# MCU.net
KiCad netlist of a schematic drawn in Altium Designer
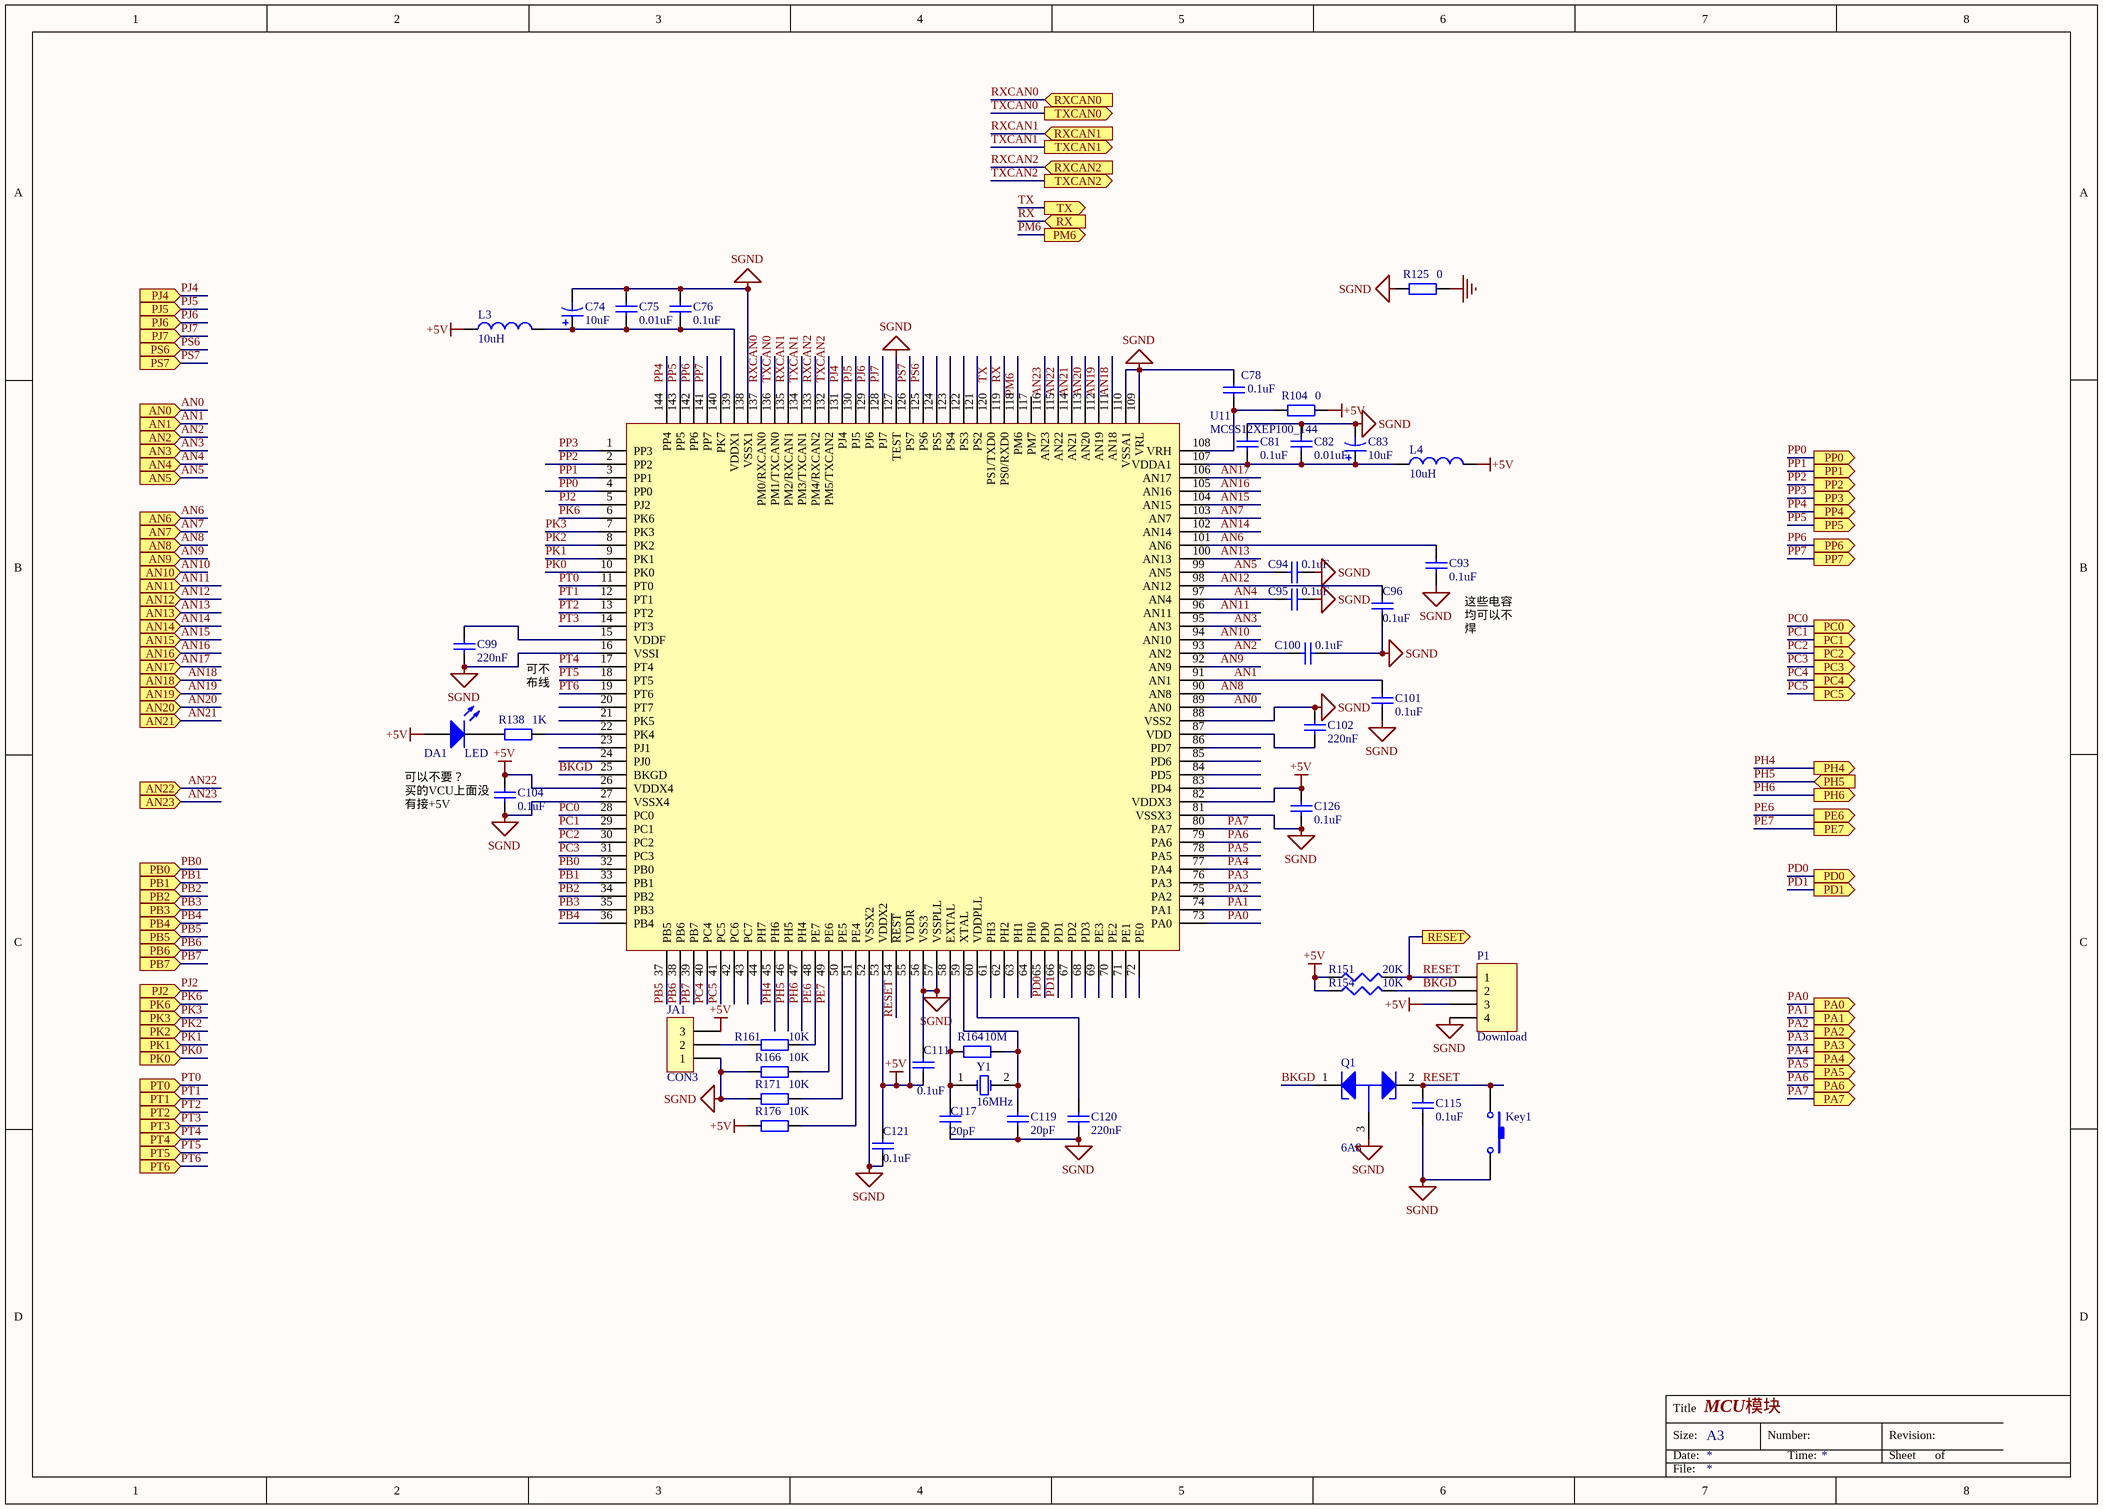
[diagram p0: MCU模块.SchDoc]

(export (version "E")
  (design (tool "Eeschema 10.0.6"))
  (components
    (comp (ref "C74")
      (value "10uF")
      (footprint "RES1206")
      (description "Polarized Capacitor (Radial)")
      (fields (field (name "Comment") "Cap Pol1") (field (name "PUBLISHER") "Altium Limited"))
      (libsource (lib "Miscellaneous Devices") (part "Cap Pol1"))
    )
    (comp (ref "C75")
      (value "0.01uF")
      (footprint "0603-L")
      (description "Capacitor")
      (fields (field (name "Comment") "Cap") (field (name "PUBLISHER") "Altium Limited"))
      (libsource (lib "Miscellaneous Devices") (part "Cap"))
    )
    (comp (ref "C76")
      (value "0.1uF")
      (footprint "0603-L")
      (description "Ceramic, X7R, 100V, 10%, 0603")
      (fields (field (name "Comment") "Cap") (field (name "PUBLISHER") "Altium Limited"))
      (libsource (lib "Resistor") (part "CC0603KRX7R0BB104"))
    )
    (comp (ref "C78")
      (value "0.1uF")
      (footprint "0603-L")
      (description "Ceramic, X7R, 100V, 10%, 0603")
      (fields (field (name "Comment") "Cap") (field (name "PUBLISHER") "Altium Limited"))
      (libsource (lib "Resistor") (part "CC0603KRX7R0BB104"))
    )
    (comp (ref "C81")
      (value "0.1uF")
      (footprint "0603-L")
      (description "Ceramic, X7R, 100V, 10%, 0603")
      (fields (field (name "Comment") "Cap") (field (name "PUBLISHER") "Altium Limited"))
      (libsource (lib "Resistor") (part "CC0603KRX7R0BB104"))
    )
    (comp (ref "C82")
      (value "0.01uF")
      (footprint "0603-L")
      (description "Capacitor")
      (fields (field (name "Comment") "Cap") (field (name "PUBLISHER") "Altium Limited"))
      (libsource (lib "Miscellaneous Devices") (part "Cap"))
    )
    (comp (ref "C83")
      (value "10uF")
      (footprint "RES1206")
      (description "Polarized Capacitor (Radial)")
      (fields (field (name "Comment") "Cap Pol1") (field (name "PUBLISHER") "Altium Limited"))
      (libsource (lib "Miscellaneous Devices") (part "Cap Pol1"))
    )
    (comp (ref "C93")
      (value "0.1uF")
      (footprint "0603-L")
      (description "Ceramic, X7R, 100V, 10%, 0603")
      (fields (field (name "Comment") "Cap") (field (name "PUBLISHER") "Altium Limited"))
      (libsource (lib "Resistor") (part "CC0603KRX7R0BB104"))
    )
    (comp (ref "C94")
      (value "0.1uF")
      (footprint "0603-L")
      (description "Ceramic, X7R, 100V, 10%, 0603")
      (fields (field (name "Comment") "Cap") (field (name "PUBLISHER") "Altium Limited"))
      (libsource (lib "Resistor") (part "CC0603KRX7R0BB104"))
    )
    (comp (ref "C95")
      (value "0.1uF")
      (footprint "0603-L")
      (description "Ceramic, X7R, 100V, 10%, 0603")
      (fields (field (name "Comment") "Cap") (field (name "PUBLISHER") "Altium Limited"))
      (libsource (lib "Resistor") (part "CC0603KRX7R0BB104"))
    )
    (comp (ref "C96")
      (value "0.1uF")
      (footprint "0603-L")
      (description "Ceramic, X7R, 100V, 10%, 0603")
      (fields (field (name "Comment") "Cap") (field (name "PUBLISHER") "Altium Limited"))
      (libsource (lib "Resistor") (part "CC0603KRX7R0BB104"))
    )
    (comp (ref "C99")
      (value "220nF")
      (footprint "RES1206")
      (description "Capacitor")
      (fields (field (name "Comment") "Cap") (field (name "PUBLISHER") "Altium Limited"))
      (libsource (lib "Miscellaneous Devices") (part "Cap"))
    )
    (comp (ref "C100")
      (value "0.1uF")
      (footprint "0603-L")
      (description "Ceramic, X7R, 100V, 10%, 0603")
      (fields (field (name "Comment") "Cap") (field (name "PUBLISHER") "Altium Limited"))
      (libsource (lib "Resistor") (part "CC0603KRX7R0BB104"))
    )
    (comp (ref "C101")
      (value "0.1uF")
      (footprint "0603-L")
      (description "Ceramic, X7R, 100V, 10%, 0603")
      (fields (field (name "Comment") "Cap") (field (name "PUBLISHER") "Altium Limited"))
      (libsource (lib "Resistor") (part "CC0603KRX7R0BB104"))
    )
    (comp (ref "C102")
      (value "220nF")
      (footprint "RES1206")
      (description "Capacitor")
      (fields (field (name "Comment") "Cap") (field (name "PUBLISHER") "Altium Limited"))
      (libsource (lib "Miscellaneous Devices") (part "Cap"))
    )
    (comp (ref "C104")
      (value "0.1uF")
      (footprint "0603-L")
      (description "Ceramic, X7R, 100V, 10%, 0603")
      (fields (field (name "Comment") "Cap") (field (name "PUBLISHER") "Altium Limited"))
      (libsource (lib "Resistor") (part "CC0603KRX7R0BB104"))
    )
    (comp (ref "C111")
      (value "0.1uF")
      (footprint "0603-L")
      (description "Ceramic, X7R, 100V, 10%, 0603")
      (fields (field (name "Comment") "Cap") (field (name "PUBLISHER") "Altium Limited"))
      (libsource (lib "Resistor") (part "CC0603KRX7R0BB104"))
    )
    (comp (ref "C115")
      (value "0.1uF")
      (footprint "0603-L")
      (description "Ceramic, X7R, 100V, 10%, 0603")
      (fields (field (name "Comment") "Cap") (field (name "PUBLISHER") "Altium Limited"))
      (libsource (lib "Resistor") (part "CC0603KRX7R0BB104"))
    )
    (comp (ref "C117")
      (value "20pF")
      (footprint "RES0805")
      (description "Capacitor")
      (fields (field (name "Comment") "Cap") (field (name "PUBLISHER") "Altium Limited"))
      (libsource (lib "Miscellaneous Devices") (part "Cap"))
    )
    (comp (ref "C119")
      (value "20pF")
      (footprint "RES0805")
      (description "Capacitor")
      (fields (field (name "Comment") "Cap") (field (name "PUBLISHER") "Altium Limited"))
      (libsource (lib "Miscellaneous Devices") (part "Cap"))
    )
    (comp (ref "C120")
      (value "220nF")
      (footprint "RES1206")
      (description "Capacitor")
      (fields (field (name "Comment") "Cap") (field (name "PUBLISHER") "Altium Limited"))
      (libsource (lib "Miscellaneous Devices") (part "Cap"))
    )
    (comp (ref "C121")
      (value "0.1uF")
      (footprint "0603-L")
      (description "Ceramic, X7R, 100V, 10%, 0603")
      (fields (field (name "Comment") "Cap") (field (name "PUBLISHER") "Altium Limited"))
      (libsource (lib "Resistor") (part "CC0603KRX7R0BB104"))
    )
    (comp (ref "C126")
      (value "0.1uF")
      (footprint "0603-L")
      (description "Ceramic, X7R, 100V, 10%, 0603")
      (fields (field (name "Comment") "Cap") (field (name "PUBLISHER") "Altium Limited"))
      (libsource (lib "Resistor") (part "CC0603KRX7R0BB104"))
    )
    (comp (ref "DA1")
      (value "LED")
      (footprint "0603-L")
      (description "Typical INFRARED GaAs LED")
      (fields (field (name "PUBLISHER") "Altium Limited"))
      (libsource (lib "Miscellaneous Devices") (part "LED0"))
    )
    (comp (ref "JA1")
      (value "CON3")
      (footprint "Miscellaneous Connectors:HDR1X3")
      (libsource (lib "MC9S12XE Library") (part "CON3"))
    )
    (comp (ref "Key1")
      (value "SW-PB")
      (footprint "KEY")
      (description "Switch")
      (fields (field (name "PUBLISHER") "Altium Limited"))
      (libsource (lib "Miscellaneous Devices") (part "SW-PB"))
    )
    (comp (ref "L3")
      (value "10uH")
      (footprint "RES1206")
      (description "Inductor")
      (fields (field (name "PUBLISHER") "Altium Limited"))
      (libsource (lib "Miscellaneous Devices") (part "Inductor"))
    )
    (comp (ref "L4")
      (value "10uH")
      (footprint "RES1206")
      (description "Inductor")
      (fields (field (name "PUBLISHER") "Altium Limited"))
      (libsource (lib "Miscellaneous Devices") (part "Inductor"))
    )
    (comp (ref "P1")
      (value "Download")
      (footprint "HDR1X4")
      (description "Header, 4-Pin")
      (fields (field (name "PUBLISHER") "Altium Limited"))
      (libsource (lib "Miscellaneous Connectors") (part "Header 4"))
    )
    (comp (ref "Q1") (value "6A8") (footprint "transistors") (libsource (lib "整车控制器") (part "6A8")))
    (comp (ref "R104")
      (value "0")
      (footprint "RES1206")
      (description "Resistor")
      (fields (field (name "Comment") "Res2") (field (name "PUBLISHER") "Altium Limited"))
      (libsource (lib "Miscellaneous Devices") (part "Res2"))
    )
    (comp (ref "R125")
      (value "0")
      (footprint "RES1206")
      (description "Resistor")
      (fields (field (name "Comment") "Res2") (field (name "PUBLISHER") "Altium Limited"))
      (libsource (lib "Miscellaneous Devices") (part "Res2"))
    )
    (comp (ref "R138")
      (value "1K")
      (footprint "0603-L")
      (description "Resistor")
      (fields (field (name "Comment") "Res2") (field (name "PUBLISHER") "Altium Limited"))
      (libsource (lib "Miscellaneous Devices") (part "Res2"))
    )
    (comp (ref "R151")
      (value "20K")
      (footprint "0603-L")
      (description "Resistor")
      (fields (field (name "Comment") "Res3") (field (name "PUBLISHER") "Altium Limited"))
      (libsource (lib "Miscellaneous Devices") (part "Res3"))
    )
    (comp (ref "R154")
      (value "10K")
      (footprint "0603-L")
      (description "Resistor")
      (fields (field (name "Comment") "Res3") (field (name "PUBLISHER") "Altium Limited"))
      (libsource (lib "Miscellaneous Devices") (part "Res3"))
    )
    (comp (ref "R161")
      (value "10K")
      (footprint "0603-L")
      (description "Resistor")
      (fields (field (name "Comment") "Res2") (field (name "PUBLISHER") "Altium Limited"))
      (libsource (lib "Miscellaneous Devices") (part "Res2"))
    )
    (comp (ref "R164")
      (value "10M")
      (footprint "0603-L")
      (description "Resistor")
      (fields (field (name "Comment") "Res2") (field (name "PUBLISHER") "Altium Limited"))
      (libsource (lib "Miscellaneous Devices") (part "Res2"))
    )
    (comp (ref "R166")
      (value "10K")
      (footprint "0603-L")
      (description "Resistor")
      (fields (field (name "Comment") "Res2") (field (name "PUBLISHER") "Altium Limited"))
      (libsource (lib "Miscellaneous Devices") (part "Res2"))
    )
    (comp (ref "R171")
      (value "10K")
      (footprint "0603-L")
      (description "Resistor")
      (fields (field (name "Comment") "Res2") (field (name "PUBLISHER") "Altium Limited"))
      (libsource (lib "Miscellaneous Devices") (part "Res2"))
    )
    (comp (ref "R176")
      (value "10K")
      (footprint "0603-L")
      (description "Resistor")
      (fields (field (name "Comment") "Res2") (field (name "PUBLISHER") "Altium Limited"))
      (libsource (lib "Miscellaneous Devices") (part "Res2"))
    )
    (comp (ref "U11")
      (value "MC9S12XEP100_144")
      (footprint "MC9S12XEP100RMV1")
      (libsource (lib "BMS") (part "MC9S12XEP100_144"))
    )
    (comp (ref "Y1")
      (value "16MHz")
      (footprint "XTAL1_1")
      (description "Crystal Oscillator")
      (fields (field (name "PUBLISHER") "Altium Limited"))
      (libsource (lib "Miscellaneous Devices") (part "XTAL"))
    )
  )
  (nets
    (net (code "1") (name "+5V") (class "Default")
      (node (ref "C104") (pin "1") (pinfunction "1_1") (pintype "passive"))
      (node (ref "C111") (pin "1") (pinfunction "1_1") (pintype "passive"))
      (node (ref "C121") (pin "2") (pinfunction "2_2") (pintype "passive"))
      (node (ref "C126") (pin "1") (pinfunction "1_1") (pintype "passive"))
      (node (ref "DA1") (pin "1") (pinfunction "A_1") (pintype "passive"))
      (node (ref "JA1") (pin "3") (pinfunction "3_3") (pintype "passive"))
      (node (ref "L3") (pin "1") (pinfunction "1_1") (pintype "passive"))
      (node (ref "L4") (pin "2") (pinfunction "2_2") (pintype "passive"))
      (node (ref "P1") (pin "3") (pinfunction "3_3") (pintype "passive"))
      (node (ref "R104") (pin "2") (pinfunction "2_2") (pintype "passive"))
      (node (ref "R151") (pin "1") (pinfunction "1_1") (pintype "passive"))
      (node (ref "R154") (pin "1") (pinfunction "1_1") (pintype "passive"))
      (node (ref "R176") (pin "1") (pinfunction "1_1") (pintype "passive"))
      (node (ref "U11") (pin "26") (pinfunction "VDDX4_26") (pintype "passive"))
      (node (ref "U11") (pin "53") (pinfunction "VDDX2_53") (pintype "passive"))
      (node (ref "U11") (pin "55") (pinfunction "VDDR_55") (pintype "passive"))
      (node (ref "U11") (pin "82") (pinfunction "VDDX3_82") (pintype "passive"))
    )
    (net (code "2") (name "/AN0") (class "Default")
      (node (ref "U11") (pin "89") (pinfunction "AN0_89") (pintype "passive"))
    )
    (net (code "3") (name "/AN1") (class "Default")
      (node (ref "C101") (pin "1") (pinfunction "1_1") (pintype "passive"))
      (node (ref "U11") (pin "91") (pinfunction "AN1_91") (pintype "passive"))
    )
    (net (code "4") (name "/AN2") (class "Default")
      (node (ref "C100") (pin "2") (pinfunction "2_2") (pintype "passive"))
      (node (ref "U11") (pin "93") (pinfunction "AN2_93") (pintype "passive"))
    )
    (net (code "5") (name "/AN3") (class "Default")
      (node (ref "U11") (pin "95") (pinfunction "AN3_95") (pintype "passive"))
    )
    (net (code "6") (name "/AN4") (class "Default")
      (node (ref "C95") (pin "2") (pinfunction "2_2") (pintype "passive"))
      (node (ref "U11") (pin "97") (pinfunction "AN4_97") (pintype "passive"))
    )
    (net (code "7") (name "/AN5") (class "Default")
      (node (ref "C94") (pin "2") (pinfunction "2_2") (pintype "passive"))
      (node (ref "U11") (pin "99") (pinfunction "AN5_99") (pintype "passive"))
    )
    (net (code "8") (name "/AN6") (class "Default")
      (node (ref "C93") (pin "2") (pinfunction "2_2") (pintype "passive"))
      (node (ref "U11") (pin "101") (pinfunction "AN6_101") (pintype "passive"))
    )
    (net (code "9") (name "/AN7") (class "Default")
      (node (ref "U11") (pin "103") (pinfunction "AN7_103") (pintype "passive"))
    )
    (net (code "10") (name "/AN8") (class "Default")
      (node (ref "U11") (pin "90") (pinfunction "AN8_90") (pintype "passive"))
    )
    (net (code "11") (name "/AN9") (class "Default")
      (node (ref "U11") (pin "92") (pinfunction "AN9_92") (pintype "passive"))
    )
    (net (code "12") (name "/AN10") (class "Default")
      (node (ref "U11") (pin "94") (pinfunction "AN10_94") (pintype "passive"))
    )
    (net (code "13") (name "/AN11") (class "Default")
      (node (ref "U11") (pin "96") (pinfunction "AN11_96") (pintype "passive"))
    )
    (net (code "14") (name "/AN12") (class "Default")
      (node (ref "C96") (pin "1") (pinfunction "1_1") (pintype "passive"))
      (node (ref "U11") (pin "98") (pinfunction "AN12_98") (pintype "passive"))
    )
    (net (code "15") (name "/AN13") (class "Default")
      (node (ref "U11") (pin "100") (pinfunction "AN13_100") (pintype "passive"))
    )
    (net (code "16") (name "/AN14") (class "Default")
      (node (ref "U11") (pin "102") (pinfunction "AN14_102") (pintype "passive"))
    )
    (net (code "17") (name "/AN15") (class "Default")
      (node (ref "U11") (pin "104") (pinfunction "AN15_104") (pintype "passive"))
    )
    (net (code "18") (name "/AN16") (class "Default")
      (node (ref "U11") (pin "105") (pinfunction "AN16_105") (pintype "passive"))
    )
    (net (code "19") (name "/AN17") (class "Default")
      (node (ref "U11") (pin "106") (pinfunction "AN17_106") (pintype "passive"))
    )
    (net (code "20") (name "/AN18") (class "Default")
      (node (ref "U11") (pin "111") (pinfunction "AN18_111") (pintype "passive"))
    )
    (net (code "21") (name "/AN19") (class "Default")
      (node (ref "U11") (pin "112") (pinfunction "AN19_112") (pintype "passive"))
    )
    (net (code "22") (name "/AN20") (class "Default")
      (node (ref "U11") (pin "113") (pinfunction "AN20_113") (pintype "passive"))
    )
    (net (code "23") (name "/AN21") (class "Default")
      (node (ref "U11") (pin "114") (pinfunction "AN21_114") (pintype "passive"))
    )
    (net (code "24") (name "/AN22") (class "Default")
      (node (ref "U11") (pin "115") (pinfunction "AN22_115") (pintype "passive"))
    )
    (net (code "25") (name "/AN23") (class "Default")
      (node (ref "U11") (pin "116") (pinfunction "AN23_116") (pintype "passive"))
    )
    (net (code "26") (name "/BKGD") (class "Default")
      (node (ref "P1") (pin "2") (pinfunction "2_2") (pintype "passive"))
      (node (ref "Q1") (pin "1") (pinfunction "B_1") (pintype "passive"))
      (node (ref "R154") (pin "2") (pinfunction "2_2") (pintype "passive"))
      (node (ref "U11") (pin "25") (pinfunction "BKGD_25") (pintype "passive"))
    )
    (net (code "27") (name "/PA0") (class "Default")
      (node (ref "U11") (pin "73") (pinfunction "PA0_73") (pintype "passive"))
    )
    (net (code "28") (name "/PA1") (class "Default")
      (node (ref "U11") (pin "74") (pinfunction "PA1_74") (pintype "passive"))
    )
    (net (code "29") (name "/PA2") (class "Default")
      (node (ref "U11") (pin "75") (pinfunction "PA2_75") (pintype "passive"))
    )
    (net (code "30") (name "/PA3") (class "Default")
      (node (ref "U11") (pin "76") (pinfunction "PA3_76") (pintype "passive"))
    )
    (net (code "31") (name "/PA4") (class "Default")
      (node (ref "U11") (pin "77") (pinfunction "PA4_77") (pintype "passive"))
    )
    (net (code "32") (name "/PA5") (class "Default")
      (node (ref "U11") (pin "78") (pinfunction "PA5_78") (pintype "passive"))
    )
    (net (code "33") (name "/PA6") (class "Default")
      (node (ref "U11") (pin "79") (pinfunction "PA6_79") (pintype "passive"))
    )
    (net (code "34") (name "/PA7") (class "Default")
      (node (ref "U11") (pin "80") (pinfunction "PA7_80") (pintype "passive"))
    )
    (net (code "35") (name "/PB0") (class "Default")
      (node (ref "U11") (pin "32") (pinfunction "PB0_32") (pintype "passive"))
    )
    (net (code "36") (name "/PB1") (class "Default")
      (node (ref "U11") (pin "33") (pinfunction "PB1_33") (pintype "passive"))
    )
    (net (code "37") (name "/PB2") (class "Default")
      (node (ref "U11") (pin "34") (pinfunction "PB2_34") (pintype "passive"))
    )
    (net (code "38") (name "/PB3") (class "Default")
      (node (ref "U11") (pin "35") (pinfunction "PB3_35") (pintype "passive"))
    )
    (net (code "39") (name "/PB4") (class "Default")
      (node (ref "U11") (pin "36") (pinfunction "PB4_36") (pintype "passive"))
    )
    (net (code "40") (name "/PB5") (class "Default")
      (node (ref "U11") (pin "37") (pinfunction "PB5_37") (pintype "passive"))
    )
    (net (code "41") (name "/PB6") (class "Default")
      (node (ref "U11") (pin "38") (pinfunction "PB6_38") (pintype "passive"))
    )
    (net (code "42") (name "/PB7") (class "Default")
      (node (ref "U11") (pin "39") (pinfunction "PB7_39") (pintype "passive"))
    )
    (net (code "43") (name "/PC0") (class "Default")
      (node (ref "U11") (pin "28") (pinfunction "PC0_28") (pintype "passive"))
    )
    (net (code "44") (name "/PC1") (class "Default")
      (node (ref "U11") (pin "29") (pinfunction "PC1_29") (pintype "passive"))
    )
    (net (code "45") (name "/PC2") (class "Default")
      (node (ref "U11") (pin "30") (pinfunction "PC2_30") (pintype "passive"))
    )
    (net (code "46") (name "/PC3") (class "Default")
      (node (ref "U11") (pin "31") (pinfunction "PC3_31") (pintype "passive"))
    )
    (net (code "47") (name "/PC4") (class "Default")
      (node (ref "U11") (pin "40") (pinfunction "PC4_40") (pintype "passive"))
    )
    (net (code "48") (name "/PC5") (class "Default")
      (node (ref "U11") (pin "41") (pinfunction "PC5_41") (pintype "passive"))
    )
    (net (code "49") (name "/PD0") (class "Default")
      (node (ref "U11") (pin "65") (pinfunction "PD0_65") (pintype "passive"))
    )
    (net (code "50") (name "/PD1") (class "Default")
      (node (ref "U11") (pin "66") (pinfunction "PD1_66") (pintype "passive"))
    )
    (net (code "51") (name "/PE6") (class "Default")
      (node (ref "R161") (pin "2") (pinfunction "2_2") (pintype "passive"))
      (node (ref "U11") (pin "48") (pinfunction "PE7_48") (pintype "passive"))
    )
    (net (code "52") (name "/PE7") (class "Default")
      (node (ref "R166") (pin "2") (pinfunction "2_2") (pintype "passive"))
      (node (ref "U11") (pin "49") (pinfunction "PE6_49") (pintype "passive"))
    )
    (net (code "53") (name "/PH4") (class "Default")
      (node (ref "U11") (pin "45") (pinfunction "PH6_45") (pintype "passive"))
    )
    (net (code "54") (name "/PH5") (class "Default")
      (node (ref "U11") (pin "46") (pinfunction "PH5_46") (pintype "passive"))
    )
    (net (code "55") (name "/PH6") (class "Default")
      (node (ref "U11") (pin "47") (pinfunction "PH4_47") (pintype "passive"))
    )
    (net (code "56") (name "/PJ2") (class "Default")
      (node (ref "U11") (pin "5") (pinfunction "PJ2_5") (pintype "passive"))
    )
    (net (code "57") (name "/PJ4") (class "Default")
      (node (ref "U11") (pin "131") (pinfunction "PJ4_131") (pintype "passive"))
    )
    (net (code "58") (name "/PJ5") (class "Default")
      (node (ref "U11") (pin "130") (pinfunction "PJ5_130") (pintype "passive"))
    )
    (net (code "59") (name "/PJ6") (class "Default")
      (node (ref "U11") (pin "129") (pinfunction "PJ6_129") (pintype "passive"))
    )
    (net (code "60") (name "/PJ7") (class "Default")
      (node (ref "U11") (pin "128") (pinfunction "PJ7_128") (pintype "passive"))
    )
    (net (code "61") (name "/PK0") (class "Default")
      (node (ref "U11") (pin "10") (pinfunction "PK0_10") (pintype "passive"))
    )
    (net (code "62") (name "/PK1") (class "Default")
      (node (ref "U11") (pin "9") (pinfunction "PK1_9") (pintype "passive"))
    )
    (net (code "63") (name "/PK2") (class "Default")
      (node (ref "U11") (pin "8") (pinfunction "PK2_8") (pintype "passive"))
    )
    (net (code "64") (name "/PK3") (class "Default")
      (node (ref "U11") (pin "7") (pinfunction "PK3_7") (pintype "passive"))
    )
    (net (code "65") (name "/PK6") (class "Default")
      (node (ref "U11") (pin "6") (pinfunction "PK6_6") (pintype "passive"))
    )
    (net (code "66") (name "/PM6") (class "Default")
      (node (ref "U11") (pin "118") (pinfunction "PM6_118") (pintype "passive"))
    )
    (net (code "67") (name "/PP0") (class "Default")
      (node (ref "U11") (pin "4") (pinfunction "PP0_4") (pintype "passive"))
    )
    (net (code "68") (name "/PP1") (class "Default")
      (node (ref "U11") (pin "3") (pinfunction "PP1_3") (pintype "passive"))
    )
    (net (code "69") (name "/PP2") (class "Default")
      (node (ref "U11") (pin "2") (pinfunction "PP2_2") (pintype "passive"))
    )
    (net (code "70") (name "/PP3") (class "Default")
      (node (ref "U11") (pin "1") (pinfunction "PP3_1") (pintype "passive"))
    )
    (net (code "71") (name "/PP4") (class "Default")
      (node (ref "U11") (pin "144") (pinfunction "PP4_144") (pintype "passive"))
    )
    (net (code "72") (name "/PP5") (class "Default")
      (node (ref "U11") (pin "143") (pinfunction "PP5_143") (pintype "passive"))
    )
    (net (code "73") (name "/PP6") (class "Default")
      (node (ref "U11") (pin "142") (pinfunction "PP6_142") (pintype "passive"))
    )
    (net (code "74") (name "/PP7") (class "Default")
      (node (ref "U11") (pin "141") (pinfunction "PP7_141") (pintype "passive"))
    )
    (net (code "75") (name "/PS6") (class "Default")
      (node (ref "U11") (pin "125") (pinfunction "PS6_125") (pintype "passive"))
    )
    (net (code "76") (name "/PS7") (class "Default")
      (node (ref "U11") (pin "126") (pinfunction "PS7_126") (pintype "passive"))
    )
    (net (code "77") (name "/PT0") (class "Default")
      (node (ref "U11") (pin "11") (pinfunction "PT0_11") (pintype "passive"))
    )
    (net (code "78") (name "/PT1") (class "Default")
      (node (ref "U11") (pin "12") (pinfunction "PT1_12") (pintype "passive"))
    )
    (net (code "79") (name "/PT2") (class "Default")
      (node (ref "U11") (pin "13") (pinfunction "PT2_13") (pintype "passive"))
    )
    (net (code "80") (name "/PT3") (class "Default")
      (node (ref "U11") (pin "14") (pinfunction "PT3_14") (pintype "passive"))
    )
    (net (code "81") (name "/PT4") (class "Default")
      (node (ref "U11") (pin "17") (pinfunction "PT4_17") (pintype "passive"))
    )
    (net (code "82") (name "/PT5") (class "Default")
      (node (ref "U11") (pin "18") (pinfunction "PT5_18") (pintype "passive"))
    )
    (net (code "83") (name "/PT6") (class "Default")
      (node (ref "U11") (pin "19") (pinfunction "PT6_19") (pintype "passive"))
    )
    (net (code "84") (name "/RESET") (class "Default")
      (node (ref "C115") (pin "2") (pinfunction "2_2") (pintype "passive"))
      (node (ref "Key1") (pin "1") (pinfunction "1_1") (pintype "passive"))
      (node (ref "P1") (pin "1") (pinfunction "1_1") (pintype "passive"))
      (node (ref "Q1") (pin "2") (pinfunction "E_2") (pintype "passive"))
      (node (ref "R151") (pin "2") (pinfunction "2_2") (pintype "passive"))
      (node (ref "U11") (pin "54") (pinfunction "~{REST}_54") (pintype "passive"))
    )
    (net (code "85") (name "/RX") (class "Default")
      (node (ref "U11") (pin "119") (pinfunction "PS0/RXD0_119") (pintype "passive"))
    )
    (net (code "86") (name "/RXCAN0") (class "Default")
      (node (ref "U11") (pin "137") (pinfunction "PM0/RXCAN0_137") (pintype "passive"))
    )
    (net (code "87") (name "/RXCAN1") (class "Default")
      (node (ref "U11") (pin "135") (pinfunction "PM2/RXCAN1_135") (pintype "passive"))
    )
    (net (code "88") (name "/RXCAN2") (class "Default")
      (node (ref "U11") (pin "133") (pinfunction "PM4/RXCAN2_133") (pintype "passive"))
    )
    (net (code "89") (name "/TX") (class "Default")
      (node (ref "U11") (pin "120") (pinfunction "PS1/TXD0_120") (pintype "passive"))
    )
    (net (code "90") (name "/TXCAN0") (class "Default")
      (node (ref "U11") (pin "136") (pinfunction "PM1/TXCAN0_136") (pintype "passive"))
    )
    (net (code "91") (name "/TXCAN1") (class "Default")
      (node (ref "U11") (pin "134") (pinfunction "PM3/TXCAN1_134") (pintype "passive"))
    )
    (net (code "92") (name "/TXCAN2") (class "Default")
      (node (ref "U11") (pin "132") (pinfunction "PM5/TXCAN2_132") (pintype "passive"))
    )
    (net (code "93") (name "GND") (class "Default")
      (node (ref "R125") (pin "2") (pinfunction "2_2") (pintype "passive"))
    )
    (net (code "94") (name "Net-(DA1-K)") (class "Default")
      (node (ref "DA1") (pin "2") (pinfunction "K_2") (pintype "passive"))
      (node (ref "R138") (pin "1") (pinfunction "1_1") (pintype "passive"))
    )
    (net (code "95") (name "Net-(JA1-Pad2)") (class "Default")
      (node (ref "JA1") (pin "2") (pinfunction "2_2") (pintype "passive"))
      (node (ref "R161") (pin "1") (pinfunction "1_1") (pintype "passive"))
    )
    (net (code "96") (name "Net-(U11-EXTAL)") (class "Default")
      (node (ref "C117") (pin "2") (pinfunction "2_2") (pintype "passive"))
      (node (ref "R164") (pin "1") (pinfunction "1_1") (pintype "passive"))
      (node (ref "U11") (pin "58") (pinfunction "EXTAL_58") (pintype "passive"))
      (node (ref "Y1") (pin "1") (pinfunction "OSC1_1") (pintype "passive"))
    )
    (net (code "97") (name "Net-(U11-PE4)") (class "Default")
      (node (ref "R176") (pin "2") (pinfunction "2_2") (pintype "passive"))
      (node (ref "U11") (pin "51") (pinfunction "PE4_51") (pintype "passive"))
    )
    (net (code "98") (name "Net-(U11-PE5)") (class "Default")
      (node (ref "R171") (pin "2") (pinfunction "2_2") (pintype "passive"))
      (node (ref "U11") (pin "50") (pinfunction "PE5_50") (pintype "passive"))
    )
    (net (code "99") (name "Net-(U11-PK4)") (class "Default")
      (node (ref "R138") (pin "2") (pinfunction "2_2") (pintype "passive"))
      (node (ref "U11") (pin "22") (pinfunction "PK4_22") (pintype "passive"))
    )
    (net (code "100") (name "Net-(U11-VDD)") (class "Default")
      (node (ref "C102") (pin "2") (pinfunction "2_2") (pintype "passive"))
      (node (ref "U11") (pin "87") (pinfunction "VDD_87") (pintype "passive"))
    )
    (net (code "101") (name "Net-(U11-VDDA1)") (class "Default")
      (node (ref "C81") (pin "2") (pinfunction "2_2") (pintype "passive"))
      (node (ref "C82") (pin "2") (pinfunction "2_2") (pintype "passive"))
      (node (ref "C83") (pin "1") (pinfunction "1_1") (pintype "passive"))
      (node (ref "L4") (pin "1") (pinfunction "1_1") (pintype "passive"))
      (node (ref "U11") (pin "107") (pinfunction "VDDA1_107") (pintype "passive"))
    )
    (net (code "102") (name "Net-(U11-VDDF)") (class "Default")
      (node (ref "C99") (pin "2") (pinfunction "2_2") (pintype "passive"))
      (node (ref "U11") (pin "15") (pinfunction "VDDF_15") (pintype "passive"))
    )
    (net (code "103") (name "Net-(U11-VDDPLL)") (class "Default")
      (node (ref "C120") (pin "2") (pinfunction "2_2") (pintype "passive"))
      (node (ref "U11") (pin "60") (pinfunction "VDDPLL_60") (pintype "passive"))
    )
    (net (code "104") (name "Net-(U11-VDDX1)") (class "Default")
      (node (ref "C74") (pin "1") (pinfunction "1_1") (pintype "passive"))
      (node (ref "C75") (pin "1") (pinfunction "1_1") (pintype "passive"))
      (node (ref "C76") (pin "1") (pinfunction "1_1") (pintype "passive"))
      (node (ref "L3") (pin "2") (pinfunction "2_2") (pintype "passive"))
      (node (ref "U11") (pin "139") (pinfunction "VDDX1_139") (pintype "passive"))
    )
    (net (code "105") (name "Net-(U11-VRH)") (class "Default")
      (node (ref "C78") (pin "1") (pinfunction "1_1") (pintype "passive"))
      (node (ref "R104") (pin "1") (pinfunction "1_1") (pintype "passive"))
      (node (ref "U11") (pin "108") (pinfunction "VRH_108") (pintype "passive"))
    )
    (net (code "106") (name "Net-(U11-XTAL)") (class "Default")
      (node (ref "C119") (pin "2") (pinfunction "2_2") (pintype "passive"))
      (node (ref "R164") (pin "2") (pinfunction "2_2") (pintype "passive"))
      (node (ref "U11") (pin "59") (pinfunction "XTAL_59") (pintype "passive"))
      (node (ref "Y1") (pin "2") (pinfunction "OSC2_2") (pintype "passive"))
    )
    (net (code "107") (name "SGND") (class "Default")
      (node (ref "C100") (pin "1") (pinfunction "1_1") (pintype "passive"))
      (node (ref "C101") (pin "2") (pinfunction "2_2") (pintype "passive"))
      (node (ref "C102") (pin "1") (pinfunction "1_1") (pintype "passive"))
      (node (ref "C104") (pin "2") (pinfunction "2_2") (pintype "passive"))
      (node (ref "C111") (pin "2") (pinfunction "2_2") (pintype "passive"))
      (node (ref "C115") (pin "1") (pinfunction "1_1") (pintype "passive"))
      (node (ref "C117") (pin "1") (pinfunction "1_1") (pintype "passive"))
      (node (ref "C119") (pin "1") (pinfunction "1_1") (pintype "passive"))
      (node (ref "C120") (pin "1") (pinfunction "1_1") (pintype "passive"))
      (node (ref "C121") (pin "1") (pinfunction "1_1") (pintype "passive"))
      (node (ref "C126") (pin "2") (pinfunction "2_2") (pintype "passive"))
      (node (ref "C74") (pin "2") (pinfunction "2_2") (pintype "passive"))
      (node (ref "C75") (pin "2") (pinfunction "2_2") (pintype "passive"))
      (node (ref "C76") (pin "2") (pinfunction "2_2") (pintype "passive"))
      (node (ref "C78") (pin "2") (pinfunction "2_2") (pintype "passive"))
      (node (ref "C81") (pin "1") (pinfunction "1_1") (pintype "passive"))
      (node (ref "C82") (pin "1") (pinfunction "1_1") (pintype "passive"))
      (node (ref "C83") (pin "2") (pinfunction "2_2") (pintype "passive"))
      (node (ref "C93") (pin "1") (pinfunction "1_1") (pintype "passive"))
      (node (ref "C94") (pin "1") (pinfunction "1_1") (pintype "passive"))
      (node (ref "C95") (pin "1") (pinfunction "1_1") (pintype "passive"))
      (node (ref "C96") (pin "2") (pinfunction "2_2") (pintype "passive"))
      (node (ref "C99") (pin "1") (pinfunction "1_1") (pintype "passive"))
      (node (ref "JA1") (pin "1") (pinfunction "1_1") (pintype "passive"))
      (node (ref "Key1") (pin "2") (pinfunction "2_2") (pintype "passive"))
      (node (ref "P1") (pin "4") (pinfunction "4_4") (pintype "passive"))
      (node (ref "Q1") (pin "3") (pinfunction "C_3") (pintype "passive"))
      (node (ref "R125") (pin "1") (pinfunction "1_1") (pintype "passive"))
      (node (ref "R166") (pin "1") (pinfunction "1_1") (pintype "passive"))
      (node (ref "R171") (pin "1") (pinfunction "1_1") (pintype "passive"))
      (node (ref "U11") (pin "109") (pinfunction "VRL_109") (pintype "passive"))
      (node (ref "U11") (pin "110") (pinfunction "VSSA1_110") (pintype "passive"))
      (node (ref "U11") (pin "127") (pinfunction "TEST_127") (pintype "passive"))
      (node (ref "U11") (pin "138") (pinfunction "VSSX1_138") (pintype "passive"))
      (node (ref "U11") (pin "16") (pinfunction "VSSI_16") (pintype "passive"))
      (node (ref "U11") (pin "27") (pinfunction "VSSX4_27") (pintype "passive"))
      (node (ref "U11") (pin "52") (pinfunction "VSSX2_52") (pintype "passive"))
      (node (ref "U11") (pin "56") (pinfunction "VSS3_56") (pintype "passive"))
      (node (ref "U11") (pin "57") (pinfunction "VSSPLL_57") (pintype "passive"))
      (node (ref "U11") (pin "81") (pinfunction "VSSX3_81") (pintype "passive"))
      (node (ref "U11") (pin "88") (pinfunction "VSS2_88") (pintype "passive"))
    )
    (net (code "108") (name "unconnected-(U11-PC6-Pad42)") (class "Default")
      (node (ref "U11") (pin "42") (pinfunction "PC6_42") (pintype "passive"))
    )
    (net (code "109") (name "unconnected-(U11-PC7-Pad43)") (class "Default")
      (node (ref "U11") (pin "43") (pinfunction "PC7_43") (pintype "passive"))
    )
    (net (code "110") (name "unconnected-(U11-PD2-Pad67)") (class "Default")
      (node (ref "U11") (pin "67") (pinfunction "PD2_67") (pintype "passive"))
    )
    (net (code "111") (name "unconnected-(U11-PD3-Pad68)") (class "Default")
      (node (ref "U11") (pin "68") (pinfunction "PD3_68") (pintype "passive"))
    )
    (net (code "112") (name "unconnected-(U11-PD4-Pad83)") (class "Default")
      (node (ref "U11") (pin "83") (pinfunction "PD4_83") (pintype "passive"))
    )
    (net (code "113") (name "unconnected-(U11-PD5-Pad84)") (class "Default")
      (node (ref "U11") (pin "84") (pinfunction "PD5_84") (pintype "passive"))
    )
    (net (code "114") (name "unconnected-(U11-PD6-Pad85)") (class "Default")
      (node (ref "U11") (pin "85") (pinfunction "PD6_85") (pintype "passive"))
    )
    (net (code "115") (name "unconnected-(U11-PD7-Pad86)") (class "Default")
      (node (ref "U11") (pin "86") (pinfunction "PD7_86") (pintype "passive"))
    )
    (net (code "116") (name "unconnected-(U11-PE0-Pad72)") (class "Default")
      (node (ref "U11") (pin "72") (pinfunction "PE0_72") (pintype "passive"))
    )
    (net (code "117") (name "unconnected-(U11-PE1-Pad71)") (class "Default")
      (node (ref "U11") (pin "71") (pinfunction "PE1_71") (pintype "passive"))
    )
    (net (code "118") (name "unconnected-(U11-PE2-Pad70)") (class "Default")
      (node (ref "U11") (pin "70") (pinfunction "PE2_70") (pintype "passive"))
    )
    (net (code "119") (name "unconnected-(U11-PE3-Pad69)") (class "Default")
      (node (ref "U11") (pin "69") (pinfunction "PE3_69") (pintype "passive"))
    )
    (net (code "120") (name "unconnected-(U11-PH0-Pad64)") (class "Default")
      (node (ref "U11") (pin "64") (pinfunction "PH0_64") (pintype "passive"))
    )
    (net (code "121") (name "unconnected-(U11-PH1-Pad63)") (class "Default")
      (node (ref "U11") (pin "63") (pinfunction "PH1_63") (pintype "passive"))
    )
    (net (code "122") (name "unconnected-(U11-PH2-Pad62)") (class "Default")
      (node (ref "U11") (pin "62") (pinfunction "PH2_62") (pintype "passive"))
    )
    (net (code "123") (name "unconnected-(U11-PH3-Pad61)") (class "Default")
      (node (ref "U11") (pin "61") (pinfunction "PH3_61") (pintype "passive"))
    )
    (net (code "124") (name "unconnected-(U11-PH7-Pad44)") (class "Default")
      (node (ref "U11") (pin "44") (pinfunction "PH7_44") (pintype "passive"))
    )
    (net (code "125") (name "unconnected-(U11-PJ0-Pad24)") (class "Default")
      (node (ref "U11") (pin "24") (pinfunction "PJ0_24") (pintype "passive"))
    )
    (net (code "126") (name "unconnected-(U11-PJ1-Pad23)") (class "Default")
      (node (ref "U11") (pin "23") (pinfunction "PJ1_23") (pintype "passive"))
    )
    (net (code "127") (name "unconnected-(U11-PK5-Pad21)") (class "Default")
      (node (ref "U11") (pin "21") (pinfunction "PK5_21") (pintype "passive"))
    )
    (net (code "128") (name "unconnected-(U11-PK7-Pad140)") (class "Default")
      (node (ref "U11") (pin "140") (pinfunction "PK7_140") (pintype "passive"))
    )
    (net (code "129") (name "unconnected-(U11-PM7-Pad117)") (class "Default")
      (node (ref "U11") (pin "117") (pinfunction "PM7_117") (pintype "passive"))
    )
    (net (code "130") (name "unconnected-(U11-PS2-Pad121)") (class "Default")
      (node (ref "U11") (pin "121") (pinfunction "PS2_121") (pintype "passive"))
    )
    (net (code "131") (name "unconnected-(U11-PS3-Pad122)") (class "Default")
      (node (ref "U11") (pin "122") (pinfunction "PS3_122") (pintype "passive"))
    )
    (net (code "132") (name "unconnected-(U11-PS4-Pad123)") (class "Default")
      (node (ref "U11") (pin "123") (pinfunction "PS4_123") (pintype "passive"))
    )
    (net (code "133") (name "unconnected-(U11-PS5-Pad124)") (class "Default")
      (node (ref "U11") (pin "124") (pinfunction "PS5_124") (pintype "passive"))
    )
    (net (code "134") (name "unconnected-(U11-PT7-Pad20)") (class "Default")
      (node (ref "U11") (pin "20") (pinfunction "PT7_20") (pintype "passive"))
    )
  )
)
